# RS232_Interface.net
KiCad netlist of a schematic drawn in Altium Designer
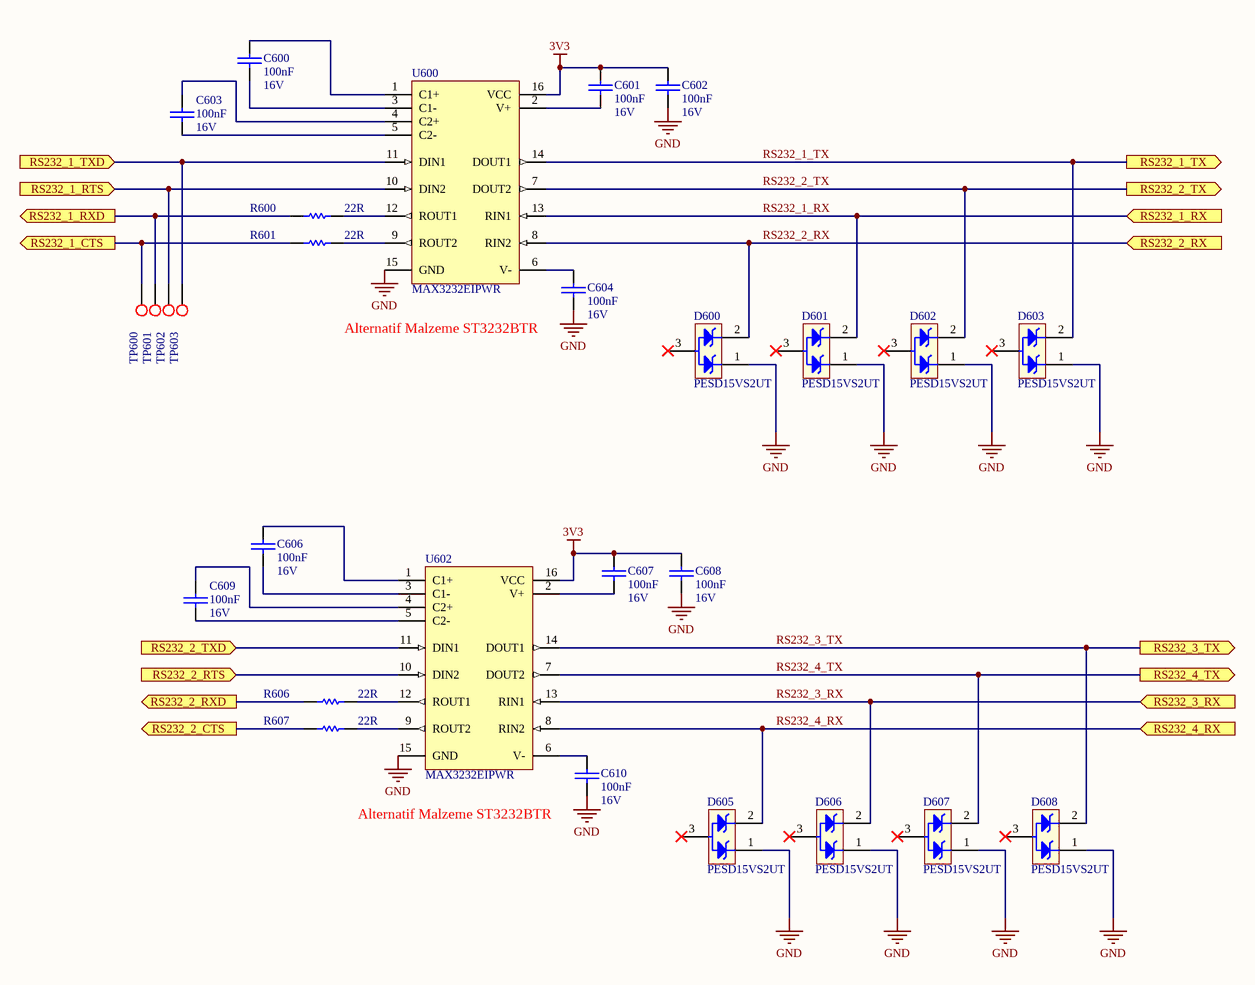
[diagram p0: RS232_Interface.SchDoc]

(export (version "E")
  (design (tool "Eeschema 10.0.6"))
  (components
    (comp (ref "C600")
      (value "100nF")
      (footprint "CAPC1005X06N")
      (description "CAP, CER, X7R, 100nF, %10, 16V, 0402")
      (fields
        (field (name "MANUFACTURER") "Murata")
        (field (name "MANUFACTURER PART NUMBER") "GRM155R71C104KA88D")
        (field (name "OPERATING VOLTAGE") "16V")
      )
      (libsource (lib "Anime_Capacitor") (part "ACC7-2100-S241-0000"))
    )
    (comp (ref "C601")
      (value "100nF")
      (footprint "CAPC1005X06N")
      (description "CAP, CER, X7R, 100nF, %10, 16V, 0402")
      (fields
        (field (name "MANUFACTURER") "Murata")
        (field (name "MANUFACTURER PART NUMBER") "GRM155R71C104KA88D")
        (field (name "OPERATING VOLTAGE") "16V")
      )
      (libsource (lib "Anime_Capacitor") (part "ACC7-2100-S241-0000"))
    )
    (comp (ref "C602")
      (value "100nF")
      (footprint "CAPC1005X06N")
      (description "CAP, CER, X7R, 100nF, %10, 16V, 0402")
      (fields
        (field (name "MANUFACTURER") "Murata")
        (field (name "MANUFACTURER PART NUMBER") "GRM155R71C104KA88D")
        (field (name "OPERATING VOLTAGE") "16V")
      )
      (libsource (lib "Anime_Capacitor") (part "ACC7-2100-S241-0000"))
    )
    (comp (ref "C603")
      (value "100nF")
      (footprint "CAPC1005X06N")
      (description "CAP, CER, X7R, 100nF, %10, 16V, 0402")
      (fields
        (field (name "MANUFACTURER") "Murata")
        (field (name "MANUFACTURER PART NUMBER") "GRM155R71C104KA88D")
        (field (name "OPERATING VOLTAGE") "16V")
      )
      (libsource (lib "Anime_Capacitor") (part "ACC7-2100-S241-0000"))
    )
    (comp (ref "C604")
      (value "100nF")
      (footprint "CAPC1005X06N")
      (description "CAP, CER, X7R, 100nF, %10, 16V, 0402")
      (fields
        (field (name "MANUFACTURER") "Murata")
        (field (name "MANUFACTURER PART NUMBER") "GRM155R71C104KA88D")
        (field (name "OPERATING VOLTAGE") "16V")
      )
      (libsource (lib "Anime_Capacitor") (part "ACC7-2100-S241-0000"))
    )
    (comp (ref "C606")
      (value "100nF")
      (footprint "CAPC1005X06N")
      (description "CAP, CER, X7R, 100nF, %10, 16V, 0402")
      (fields
        (field (name "MANUFACTURER") "Murata")
        (field (name "MANUFACTURER PART NUMBER") "GRM155R71C104KA88D")
        (field (name "OPERATING VOLTAGE") "16V")
      )
      (libsource (lib "Anime_Capacitor") (part "ACC7-2100-S241-0000"))
    )
    (comp (ref "C607")
      (value "100nF")
      (footprint "CAPC1005X06N")
      (description "CAP, CER, X7R, 100nF, %10, 16V, 0402")
      (fields
        (field (name "MANUFACTURER") "Murata")
        (field (name "MANUFACTURER PART NUMBER") "GRM155R71C104KA88D")
        (field (name "OPERATING VOLTAGE") "16V")
      )
      (libsource (lib "Anime_Capacitor") (part "ACC7-2100-S241-0000"))
    )
    (comp (ref "C608")
      (value "100nF")
      (footprint "CAPC1005X06N")
      (description "CAP, CER, X7R, 100nF, %10, 16V, 0402")
      (fields
        (field (name "MANUFACTURER") "Murata")
        (field (name "MANUFACTURER PART NUMBER") "GRM155R71C104KA88D")
        (field (name "OPERATING VOLTAGE") "16V")
      )
      (libsource (lib "Anime_Capacitor") (part "ACC7-2100-S241-0000"))
    )
    (comp (ref "C609")
      (value "100nF")
      (footprint "CAPC1005X06N")
      (description "CAP, CER, X7R, 100nF, %10, 16V, 0402")
      (fields
        (field (name "MANUFACTURER") "Murata")
        (field (name "MANUFACTURER PART NUMBER") "GRM155R71C104KA88D")
        (field (name "OPERATING VOLTAGE") "16V")
      )
      (libsource (lib "Anime_Capacitor") (part "ACC7-2100-S241-0000"))
    )
    (comp (ref "C610")
      (value "100nF")
      (footprint "CAPC1005X06N")
      (description "CAP, CER, X7R, 100nF, %10, 16V, 0402")
      (fields
        (field (name "MANUFACTURER") "Murata")
        (field (name "MANUFACTURER PART NUMBER") "GRM155R71C104KA88D")
        (field (name "OPERATING VOLTAGE") "16V")
      )
      (libsource (lib "Anime_Capacitor") (part "ACC7-2100-S241-0000"))
    )
    (comp (ref "D600")
      (value "PESD15VS2UT")
      (footprint "SOT95P230X111-3N")
      (description "Diode, TVS, ESD Protection, 15V, PESD15VS2UT, SOT-23")
      (fields (field (name "MANUFACTURER") "NXP"))
      (libsource (lib "Anime_Semiconductor") (part "AS1H-950M-SI20-0000"))
    )
    (comp (ref "D601")
      (value "PESD15VS2UT")
      (footprint "SOT95P230X111-3N")
      (description "Diode, TVS, ESD Protection, 15V, PESD15VS2UT, SOT-23")
      (fields (field (name "MANUFACTURER") "NXP"))
      (libsource (lib "Anime_Semiconductor") (part "AS1H-950M-SI20-0000"))
    )
    (comp (ref "D602")
      (value "PESD15VS2UT")
      (footprint "SOT95P230X111-3N")
      (description "Diode, TVS, ESD Protection, 15V, PESD15VS2UT, SOT-23")
      (fields (field (name "MANUFACTURER") "NXP"))
      (libsource (lib "Anime_Semiconductor") (part "AS1H-950M-SI20-0000"))
    )
    (comp (ref "D603")
      (value "PESD15VS2UT")
      (footprint "SOT95P230X111-3N")
      (description "Diode, TVS, ESD Protection, 15V, PESD15VS2UT, SOT-23")
      (fields (field (name "MANUFACTURER") "NXP"))
      (libsource (lib "Anime_Semiconductor") (part "AS1H-950M-SI20-0000"))
    )
    (comp (ref "D605")
      (value "PESD15VS2UT")
      (footprint "SOT95P230X111-3N")
      (description "Diode, TVS, ESD Protection, 15V, PESD15VS2UT, SOT-23")
      (fields (field (name "MANUFACTURER") "NXP"))
      (libsource (lib "Anime_Semiconductor") (part "AS1H-950M-SI20-0000"))
    )
    (comp (ref "D606")
      (value "PESD15VS2UT")
      (footprint "SOT95P230X111-3N")
      (description "Diode, TVS, ESD Protection, 15V, PESD15VS2UT, SOT-23")
      (fields (field (name "MANUFACTURER") "NXP"))
      (libsource (lib "Anime_Semiconductor") (part "AS1H-950M-SI20-0000"))
    )
    (comp (ref "D607")
      (value "PESD15VS2UT")
      (footprint "SOT95P230X111-3N")
      (description "Diode, TVS, ESD Protection, 15V, PESD15VS2UT, SOT-23")
      (fields (field (name "MANUFACTURER") "NXP"))
      (libsource (lib "Anime_Semiconductor") (part "AS1H-950M-SI20-0000"))
    )
    (comp (ref "D608")
      (value "PESD15VS2UT")
      (footprint "SOT95P230X111-3N")
      (description "Diode, TVS, ESD Protection, 15V, PESD15VS2UT, SOT-23")
      (fields (field (name "MANUFACTURER") "NXP"))
      (libsource (lib "Anime_Semiconductor") (part "AS1H-950M-SI20-0000"))
    )
    (comp (ref "R600")
      (value "22R")
      (footprint "RESC1005X04N")
      (description "RES, E24, Thick Film, SMD, 22R, 1%, 0.1W, 0402")
      (fields
        (field (name "MANUFACTURER") "Panasonic")
        (field (name "MANUFACTURER PART NUMBER") "ERJ-2RKF22R0X")
      )
      (libsource (lib "Anime_Resistor") (part "AR19-1220-S2B2-0000"))
    )
    (comp (ref "R601")
      (value "22R")
      (footprint "RESC1005X04N")
      (description "RES, E24, Thick Film, SMD, 22R, 1%, 0.1W, 0402")
      (fields
        (field (name "MANUFACTURER") "Panasonic")
        (field (name "MANUFACTURER PART NUMBER") "ERJ-2RKF22R0X")
      )
      (libsource (lib "Anime_Resistor") (part "AR19-1220-S2B2-0000"))
    )
    (comp (ref "R606")
      (value "22R")
      (footprint "RESC1005X04N")
      (description "RES, E24, Thick Film, SMD, 22R, 1%, 0.1W, 0402")
      (fields
        (field (name "MANUFACTURER") "Panasonic")
        (field (name "MANUFACTURER PART NUMBER") "ERJ-2RKF22R0X")
      )
      (libsource (lib "Anime_Resistor") (part "AR19-1220-S2B2-0000"))
    )
    (comp (ref "R607")
      (value "22R")
      (footprint "RESC1005X04N")
      (description "RES, E24, Thick Film, SMD, 22R, 1%, 0.1W, 0402")
      (fields
        (field (name "MANUFACTURER") "Panasonic")
        (field (name "MANUFACTURER PART NUMBER") "ERJ-2RKF22R0X")
      )
      (libsource (lib "Anime_Resistor") (part "AR19-1220-S2B2-0000"))
    )
    (comp (ref "TP600")
      (value "AEMT-C00S-1000-0000")
      (footprint "TP100")
      (description "Test Point, Circular, 1mm")
      (libsource (lib "Anime_Electromechanical") (part "AEMT-C00S-1000-0000"))
    )
    (comp (ref "TP601")
      (value "AEMT-C00S-1000-0000")
      (footprint "TP100")
      (description "Test Point, Circular, 1mm")
      (libsource (lib "Anime_Electromechanical") (part "AEMT-C00S-1000-0000"))
    )
    (comp (ref "TP602")
      (value "AEMT-C00S-1000-0000")
      (footprint "TP100")
      (description "Test Point, Circular, 1mm")
      (libsource (lib "Anime_Electromechanical") (part "AEMT-C00S-1000-0000"))
    )
    (comp (ref "TP603")
      (value "AEMT-C00S-1000-0000")
      (footprint "TP100")
      (description "Test Point, Circular, 1mm")
      (libsource (lib "Anime_Electromechanical") (part "AEMT-C00S-1000-0000"))
    )
    (comp (ref "U600")
      (value "MAX3232EIPWR")
      (footprint "TSOP65P640X120-16N")
      (description "IC, Interface, RS232 Driver, MAX3232EIPWR, TSSOP-16")
      (fields
        (field (name "MANUFACTURER") "Texas Instruments")
        (field (name "MANUFACTURER PART NUMBER") "MAX3232EIPWRQ1")
      )
      (libsource (lib "Anime_IC") (part "AT41-0000-SM90-0540"))
    )
    (comp (ref "U602")
      (value "MAX3232EIPWR")
      (footprint "TSOP65P640X120-16N")
      (description "IC, Interface, RS232 Driver, MAX3232EIPWR, TSSOP-16")
      (fields
        (field (name "MANUFACTURER") "Texas Instruments")
        (field (name "MANUFACTURER PART NUMBER") "MAX3232EIPWRQ1")
      )
      (libsource (lib "Anime_IC") (part "AT41-0000-SM90-0540"))
    )
  )
  (nets
    (net (code "1") (name "/RS232_1_CTS") (class "Default")
      (node (ref "R601") (pin "1") (pinfunction "1_1") (pintype "passive"))
      (node (ref "TP600") (pin "1") (pintype "passive"))
    )
    (net (code "2") (name "/RS232_1_RTS") (class "Default")
      (node (ref "TP602") (pin "1") (pintype "passive"))
      (node (ref "U600") (pin "10") (pinfunction "DIN2_10") (pintype "input"))
    )
    (net (code "3") (name "/RS232_1_RX") (class "Default")
      (node (ref "D601") (pin "2") (pinfunction "2_2") (pintype "passive"))
      (node (ref "U600") (pin "13") (pinfunction "RIN1_13") (pintype "input"))
    )
    (net (code "4") (name "/RS232_1_RXD") (class "Default")
      (node (ref "R600") (pin "1") (pinfunction "1_1") (pintype "passive"))
      (node (ref "TP601") (pin "1") (pintype "passive"))
    )
    (net (code "5") (name "/RS232_1_TX") (class "Default")
      (node (ref "D603") (pin "2") (pinfunction "2_2") (pintype "passive"))
      (node (ref "U600") (pin "14") (pinfunction "DOUT1_14") (pintype "output"))
    )
    (net (code "6") (name "/RS232_1_TXD") (class "Default")
      (node (ref "TP603") (pin "1") (pintype "passive"))
      (node (ref "U600") (pin "11") (pinfunction "DIN1_11") (pintype "input"))
    )
    (net (code "7") (name "/RS232_2_CTS") (class "Default")
      (node (ref "R607") (pin "1") (pinfunction "1_1") (pintype "passive"))
    )
    (net (code "8") (name "/RS232_2_RTS") (class "Default")
      (node (ref "U602") (pin "10") (pinfunction "DIN2_10") (pintype "input"))
    )
    (net (code "9") (name "/RS232_2_RX") (class "Default")
      (node (ref "D600") (pin "2") (pinfunction "2_2") (pintype "passive"))
      (node (ref "U600") (pin "8") (pinfunction "RIN2_8") (pintype "input"))
    )
    (net (code "10") (name "/RS232_2_RXD") (class "Default")
      (node (ref "R606") (pin "1") (pinfunction "1_1") (pintype "passive"))
    )
    (net (code "11") (name "/RS232_2_TX") (class "Default")
      (node (ref "D602") (pin "2") (pinfunction "2_2") (pintype "passive"))
      (node (ref "U600") (pin "7") (pinfunction "DOUT2_7") (pintype "output"))
    )
    (net (code "12") (name "/RS232_2_TXD") (class "Default")
      (node (ref "U602") (pin "11") (pinfunction "DIN1_11") (pintype "input"))
    )
    (net (code "13") (name "/RS232_3_RX") (class "Default")
      (node (ref "D606") (pin "2") (pinfunction "2_2") (pintype "passive"))
      (node (ref "U602") (pin "13") (pinfunction "RIN1_13") (pintype "input"))
    )
    (net (code "14") (name "/RS232_3_TX") (class "Default")
      (node (ref "D608") (pin "2") (pinfunction "2_2") (pintype "passive"))
      (node (ref "U602") (pin "14") (pinfunction "DOUT1_14") (pintype "output"))
    )
    (net (code "15") (name "/RS232_4_RX") (class "Default")
      (node (ref "D605") (pin "2") (pinfunction "2_2") (pintype "passive"))
      (node (ref "U602") (pin "8") (pinfunction "RIN2_8") (pintype "input"))
    )
    (net (code "16") (name "/RS232_4_TX") (class "Default")
      (node (ref "D607") (pin "2") (pinfunction "2_2") (pintype "passive"))
      (node (ref "U602") (pin "7") (pinfunction "DOUT2_7") (pintype "output"))
    )
    (net (code "17") (name "3V3") (class "Default")
      (node (ref "C601") (pin "2") (pintype "passive"))
      (node (ref "C602") (pin "2") (pintype "passive"))
      (node (ref "C607") (pin "2") (pintype "passive"))
      (node (ref "C608") (pin "2") (pintype "passive"))
      (node (ref "U600") (pin "16") (pinfunction "VCC_16") (pintype "power_in"))
      (node (ref "U602") (pin "16") (pinfunction "VCC_16") (pintype "power_in"))
    )
    (net (code "18") (name "GND") (class "Default")
      (node (ref "C602") (pin "1") (pintype "passive"))
      (node (ref "C604") (pin "1") (pintype "passive"))
      (node (ref "C608") (pin "1") (pintype "passive"))
      (node (ref "C610") (pin "1") (pintype "passive"))
      (node (ref "D600") (pin "1") (pinfunction "1_1") (pintype "passive"))
      (node (ref "D601") (pin "1") (pinfunction "1_1") (pintype "passive"))
      (node (ref "D602") (pin "1") (pinfunction "1_1") (pintype "passive"))
      (node (ref "D603") (pin "1") (pinfunction "1_1") (pintype "passive"))
      (node (ref "D605") (pin "1") (pinfunction "1_1") (pintype "passive"))
      (node (ref "D606") (pin "1") (pinfunction "1_1") (pintype "passive"))
      (node (ref "D607") (pin "1") (pinfunction "1_1") (pintype "passive"))
      (node (ref "D608") (pin "1") (pinfunction "1_1") (pintype "passive"))
      (node (ref "U600") (pin "15") (pinfunction "GND_15") (pintype "power_in"))
      (node (ref "U602") (pin "15") (pinfunction "GND_15") (pintype "power_in"))
    )
    (net (code "19") (name "Net-(U600-C1+)") (class "Default")
      (node (ref "C600") (pin "2") (pintype "passive"))
      (node (ref "U600") (pin "1") (pinfunction "C1+_1") (pintype "passive"))
    )
    (net (code "20") (name "Net-(U600-C1-)") (class "Default")
      (node (ref "C600") (pin "1") (pintype "passive"))
      (node (ref "U600") (pin "3") (pinfunction "C1-_3") (pintype "passive"))
    )
    (net (code "21") (name "Net-(U600-C2+)") (class "Default")
      (node (ref "C603") (pin "2") (pintype "passive"))
      (node (ref "U600") (pin "4") (pinfunction "C2+_4") (pintype "passive"))
    )
    (net (code "22") (name "Net-(U600-C2-)") (class "Default")
      (node (ref "C603") (pin "1") (pintype "passive"))
      (node (ref "U600") (pin "5") (pinfunction "C2-_5") (pintype "passive"))
    )
    (net (code "23") (name "Net-(U600-ROUT1)") (class "Default")
      (node (ref "R600") (pin "2") (pinfunction "2_2") (pintype "passive"))
      (node (ref "U600") (pin "12") (pinfunction "ROUT1_12") (pintype "output"))
    )
    (net (code "24") (name "Net-(U600-ROUT2)") (class "Default")
      (node (ref "R601") (pin "2") (pinfunction "2_2") (pintype "passive"))
      (node (ref "U600") (pin "9") (pinfunction "ROUT2_9") (pintype "output"))
    )
    (net (code "25") (name "Net-(U600-V+)") (class "Default")
      (node (ref "C601") (pin "1") (pintype "passive"))
      (node (ref "U600") (pin "2") (pinfunction "V+_2") (pintype "power_in"))
    )
    (net (code "26") (name "Net-(U600-V-)") (class "Default")
      (node (ref "C604") (pin "2") (pintype "passive"))
      (node (ref "U600") (pin "6") (pinfunction "V-_6") (pintype "power_in"))
    )
    (net (code "27") (name "Net-(U602-C1+)") (class "Default")
      (node (ref "C606") (pin "2") (pintype "passive"))
      (node (ref "U602") (pin "1") (pinfunction "C1+_1") (pintype "passive"))
    )
    (net (code "28") (name "Net-(U602-C1-)") (class "Default")
      (node (ref "C606") (pin "1") (pintype "passive"))
      (node (ref "U602") (pin "3") (pinfunction "C1-_3") (pintype "passive"))
    )
    (net (code "29") (name "Net-(U602-C2+)") (class "Default")
      (node (ref "C609") (pin "2") (pintype "passive"))
      (node (ref "U602") (pin "4") (pinfunction "C2+_4") (pintype "passive"))
    )
    (net (code "30") (name "Net-(U602-C2-)") (class "Default")
      (node (ref "C609") (pin "1") (pintype "passive"))
      (node (ref "U602") (pin "5") (pinfunction "C2-_5") (pintype "passive"))
    )
    (net (code "31") (name "Net-(U602-ROUT1)") (class "Default")
      (node (ref "R606") (pin "2") (pinfunction "2_2") (pintype "passive"))
      (node (ref "U602") (pin "12") (pinfunction "ROUT1_12") (pintype "output"))
    )
    (net (code "32") (name "Net-(U602-ROUT2)") (class "Default")
      (node (ref "R607") (pin "2") (pinfunction "2_2") (pintype "passive"))
      (node (ref "U602") (pin "9") (pinfunction "ROUT2_9") (pintype "output"))
    )
    (net (code "33") (name "Net-(U602-V+)") (class "Default")
      (node (ref "C607") (pin "1") (pintype "passive"))
      (node (ref "U602") (pin "2") (pinfunction "V+_2") (pintype "power_in"))
    )
    (net (code "34") (name "Net-(U602-V-)") (class "Default")
      (node (ref "C610") (pin "2") (pintype "passive"))
      (node (ref "U602") (pin "6") (pinfunction "V-_6") (pintype "power_in"))
    )
    (net (code "35") (name "unconnected-(D600-Pad3)") (class "Default")
      (node (ref "D600") (pin "3") (pinfunction "3_3") (pintype "passive+no_connect"))
    )
    (net (code "36") (name "unconnected-(D601-Pad3)") (class "Default")
      (node (ref "D601") (pin "3") (pinfunction "3_3") (pintype "passive+no_connect"))
    )
    (net (code "37") (name "unconnected-(D602-Pad3)") (class "Default")
      (node (ref "D602") (pin "3") (pinfunction "3_3") (pintype "passive+no_connect"))
    )
    (net (code "38") (name "unconnected-(D603-Pad3)") (class "Default")
      (node (ref "D603") (pin "3") (pinfunction "3_3") (pintype "passive+no_connect"))
    )
    (net (code "39") (name "unconnected-(D605-Pad3)") (class "Default")
      (node (ref "D605") (pin "3") (pinfunction "3_3") (pintype "passive+no_connect"))
    )
    (net (code "40") (name "unconnected-(D606-Pad3)") (class "Default")
      (node (ref "D606") (pin "3") (pinfunction "3_3") (pintype "passive+no_connect"))
    )
    (net (code "41") (name "unconnected-(D607-Pad3)") (class "Default")
      (node (ref "D607") (pin "3") (pinfunction "3_3") (pintype "passive+no_connect"))
    )
    (net (code "42") (name "unconnected-(D608-Pad3)") (class "Default")
      (node (ref "D608") (pin "3") (pinfunction "3_3") (pintype "passive+no_connect"))
    )
  )
)
